# sch_output.net
KiCad netlist of a schematic drawn in Altium Designer
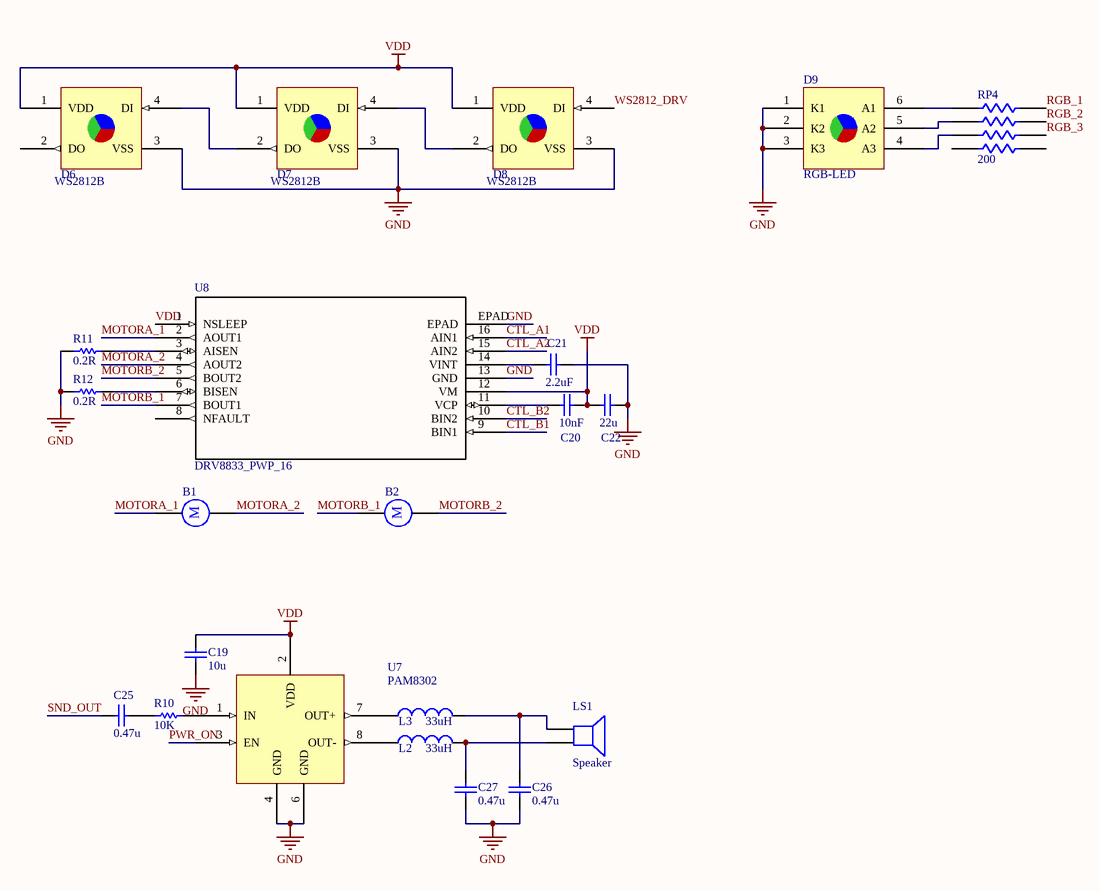
[diagram p0: sch_output.SchDoc]

(export (version "E")
  (design (tool "Eeschema 10.0.6"))
  (components
    (comp (ref "B1")
      (value "Motor")
      (footprint "RB5-10.5")
      (description "Motor, General Kind")
      (fields (field (name "PUBLISHER") "Altium Limited"))
      (libsource (lib "Miscellaneous Devices") (part "Motor"))
    )
    (comp (ref "B2")
      (value "Motor")
      (footprint "RB5-10.5")
      (description "Motor, General Kind")
      (fields (field (name "PUBLISHER") "Altium Limited"))
      (libsource (lib "Miscellaneous Devices") (part "Motor"))
    )
    (comp (ref "C19")
      (value "10u")
      (footprint "C-2012[0805]")
      (description "Capacitor (Semiconductor SIM Model)")
      (fields (field (name "Comment") "Cap Semi") (field (name "PUBLISHER") "Altium Limited"))
      (libsource (lib "Miscellaneous Devices") (part "Cap Semi"))
    )
    (comp (ref "C20")
      (value "10nF")
      (footprint "C-1608[0603]")
      (description "Capacitor (Semiconductor SIM Model)")
      (fields (field (name "Comment") "Cap Semi") (field (name "PUBLISHER") "Altium Limited"))
      (libsource (lib "Miscellaneous Devices") (part "Cap Semi"))
    )
    (comp (ref "C21")
      (value "2.2uF")
      (footprint "C-1608[0603]")
      (description "Capacitor (Semiconductor SIM Model)")
      (fields (field (name "Comment") "Cap Semi") (field (name "PUBLISHER") "Altium Limited"))
      (libsource (lib "Miscellaneous Devices") (part "Cap Semi"))
    )
    (comp (ref "C22")
      (value "22u")
      (footprint "C-2012[0805]")
      (description "Capacitor (Semiconductor SIM Model)")
      (fields (field (name "Comment") "Cap Semi") (field (name "PUBLISHER") "Altium Limited"))
      (libsource (lib "Miscellaneous Devices") (part "Cap Semi"))
    )
    (comp (ref "C25")
      (value "0.47u")
      (footprint "C-1608[0603]")
      (description "Capacitor (Semiconductor SIM Model)")
      (fields (field (name "Comment") "Cap Semi") (field (name "PUBLISHER") "Altium Limited"))
      (libsource (lib "Miscellaneous Devices") (part "Cap Semi"))
    )
    (comp (ref "C26")
      (value "0.47u")
      (footprint "C-1608[0603]")
      (description "Capacitor (Semiconductor SIM Model)")
      (fields (field (name "Comment") "Cap Semi") (field (name "PUBLISHER") "Altium Limited"))
      (libsource (lib "Miscellaneous Devices") (part "Cap Semi"))
    )
    (comp (ref "C27")
      (value "0.47u")
      (footprint "C-1608[0603]")
      (description "Capacitor (Semiconductor SIM Model)")
      (fields (field (name "Comment") "Cap Semi") (field (name "PUBLISHER") "Altium Limited"))
      (libsource (lib "Miscellaneous Devices") (part "Cap Semi"))
    )
    (comp (ref "D6") (value "WS2812B") (footprint "LED-5050-4") (libsource (lib "general") (part "WS2812B")))
    (comp (ref "D7") (value "WS2812B") (footprint "LED-5050-4") (libsource (lib "general") (part "WS2812B")))
    (comp (ref "D8") (value "WS2812B") (footprint "LED-5050-4") (libsource (lib "general") (part "WS2812B")))
    (comp (ref "D9") (value "RGB-LED") (footprint "LED-5050-6") (libsource (lib "general") (part "RGBLED")))
    (comp (ref "L2")
      (value "33uH")
      (footprint "L-1608[0603]")
      (description "Inductor")
      (fields (field (name "PUBLISHER") "Altium Limited"))
      (libsource (lib "Miscellaneous Devices") (part "Inductor"))
    )
    (comp (ref "L3")
      (value "33uH")
      (footprint "L-1608[0603]")
      (description "Inductor")
      (fields (field (name "PUBLISHER") "Altium Limited"))
      (libsource (lib "Miscellaneous Devices") (part "Inductor"))
    )
    (comp (ref "LS1")
      (value "Speaker")
      (footprint "PIN2")
      (description "Loudspeaker")
      (fields (field (name "PUBLISHER") "Altium Limited"))
      (libsource (lib "Miscellaneous Devices") (part "Speaker"))
    )
    (comp (ref "R10")
      (value "10K")
      (footprint "R-1608[0603]")
      (description "Semiconductor Resistor")
      (fields (field (name "Comment") "Res Semi") (field (name "PUBLISHER") "Altium Limited"))
      (libsource (lib "Miscellaneous Devices") (part "Res Semi"))
    )
    (comp (ref "R11")
      (value "0.2R")
      (footprint "R-3216[1206]")
      (description "Semiconductor Resistor")
      (fields (field (name "Comment") "Res Semi") (field (name "PUBLISHER") "Altium Limited"))
      (libsource (lib "Miscellaneous Devices") (part "Res Semi"))
    )
    (comp (ref "R12")
      (value "0.2R")
      (footprint "R-3216[1206]")
      (description "Semiconductor Resistor")
      (fields (field (name "Comment") "Res Semi") (field (name "PUBLISHER") "Altium Limited"))
      (libsource (lib "Miscellaneous Devices") (part "Res Semi"))
    )
    (comp (ref "RP4") (value "200") (footprint "R0603x4") (libsource (lib "general") (part "RPACK4")))
    (comp (ref "U7") (value "PAM8302") (footprint "SOP8-3D") (libsource (lib "general") (part "PAM8302")))
    (comp (ref "U8")
      (value "DRV8833_PWP_16")
      (footprint "PWP16_2P31X2P46")
      (description "Imported")
      (fields
        (field (name "MANUFACTURER") "Texas Instruments")
        (field (name "GENERIC_PART_NUMBER") "DRV8833")
      )
      (libsource (lib "DRV8833") (part "DRV8833_PWP_16"))
    )
  )
  (nets
    (net (code "1") (name "/CTL_A1") (class "Default")
      (node (ref "U8") (pin "16") (pinfunction "AIN1_16") (pintype "input"))
    )
    (net (code "2") (name "/CTL_A2") (class "Default")
      (node (ref "U8") (pin "15") (pinfunction "AIN2_15") (pintype "input"))
    )
    (net (code "3") (name "/CTL_B1") (class "Default")
      (node (ref "U8") (pin "9") (pinfunction "BIN1_9") (pintype "input"))
    )
    (net (code "4") (name "/CTL_B2") (class "Default")
      (node (ref "U8") (pin "10") (pinfunction "BIN2_10") (pintype "input"))
    )
    (net (code "5") (name "/MOTORA_1") (class "Default")
      (node (ref "B1") (pin "1") (pinfunction "1_1") (pintype "passive"))
      (node (ref "U8") (pin "2") (pinfunction "AOUT1_2") (pintype "output"))
    )
    (net (code "6") (name "/MOTORA_2") (class "Default")
      (node (ref "B1") (pin "2") (pinfunction "2_2") (pintype "passive"))
      (node (ref "U8") (pin "4") (pinfunction "AOUT2_4") (pintype "output"))
    )
    (net (code "7") (name "/MOTORB_1") (class "Default")
      (node (ref "B2") (pin "1") (pinfunction "1_1") (pintype "passive"))
      (node (ref "U8") (pin "7") (pinfunction "BOUT1_7") (pintype "output"))
    )
    (net (code "8") (name "/MOTORB_2") (class "Default")
      (node (ref "B2") (pin "2") (pinfunction "2_2") (pintype "passive"))
      (node (ref "U8") (pin "5") (pinfunction "BOUT2_5") (pintype "output"))
    )
    (net (code "9") (name "/PWR_ON") (class "Default")
      (node (ref "U7") (pin "3") (pinfunction "EN_3") (pintype "input"))
    )
    (net (code "10") (name "/RGB_1") (class "Default")
      (node (ref "RP4") (pin "8") (pinfunction "8_8") (pintype "passive"))
    )
    (net (code "11") (name "/RGB_2") (class "Default")
      (node (ref "RP4") (pin "7") (pinfunction "7_7") (pintype "passive"))
    )
    (net (code "12") (name "/RGB_3") (class "Default")
      (node (ref "RP4") (pin "6") (pinfunction "6_6") (pintype "passive"))
    )
    (net (code "13") (name "/SND_OUT") (class "Default")
      (node (ref "C25") (pin "2") (pinfunction "2_2") (pintype "passive"))
    )
    (net (code "14") (name "/WS2812_DRV") (class "Default")
      (node (ref "D8") (pin "4") (pinfunction "DI_4") (pintype "input"))
    )
    (net (code "15") (name "GND") (class "Default")
      (node (ref "C19") (pin "1") (pinfunction "1_1") (pintype "passive"))
      (node (ref "C21") (pin "1") (pinfunction "1_1") (pintype "passive"))
      (node (ref "C22") (pin "2") (pinfunction "2_2") (pintype "passive"))
      (node (ref "C26") (pin "2") (pinfunction "2_2") (pintype "passive"))
      (node (ref "C27") (pin "2") (pinfunction "2_2") (pintype "passive"))
      (node (ref "D6") (pin "3") (pinfunction "VSS_3") (pintype "power_in"))
      (node (ref "D7") (pin "3") (pinfunction "VSS_3") (pintype "power_in"))
      (node (ref "D8") (pin "3") (pinfunction "VSS_3") (pintype "power_in"))
      (node (ref "D9") (pin "1") (pinfunction "K1_1") (pintype "passive"))
      (node (ref "D9") (pin "2") (pinfunction "K2_2") (pintype "passive"))
      (node (ref "D9") (pin "3") (pinfunction "K3_3") (pintype "power_in"))
      (node (ref "R11") (pin "1") (pinfunction "1_1") (pintype "passive"))
      (node (ref "R12") (pin "1") (pinfunction "1_1") (pintype "passive"))
      (node (ref "U7") (pin "4") (pinfunction "GND_4") (pintype "power_in"))
      (node (ref "U7") (pin "6") (pinfunction "GND_6") (pintype "power_in"))
      (node (ref "U8") (pin "13") (pinfunction "GND_13") (pintype "power_in"))
      (node (ref "U8") (pin "EPAD") (pinfunction "EPAD_EPAD") (pintype "passive"))
    )
    (net (code "16") (name "Net-(C25-Pad1)") (class "Default")
      (node (ref "C25") (pin "1") (pinfunction "1_1") (pintype "passive"))
      (node (ref "R10") (pin "2") (pinfunction "2_2") (pintype "passive"))
    )
    (net (code "17") (name "Net-(C26-Pad1)") (class "Default")
      (node (ref "C26") (pin "1") (pinfunction "1_1") (pintype "passive"))
      (node (ref "L3") (pin "2") (pinfunction "2_2") (pintype "passive"))
      (node (ref "LS1") (pin "1") (pinfunction "1_1") (pintype "passive"))
    )
    (net (code "18") (name "Net-(C27-Pad1)") (class "Default")
      (node (ref "C27") (pin "1") (pinfunction "1_1") (pintype "passive"))
      (node (ref "L2") (pin "2") (pinfunction "2_2") (pintype "passive"))
      (node (ref "LS1") (pin "2") (pinfunction "2_2") (pintype "passive"))
    )
    (net (code "19") (name "Net-(D6-DI)") (class "Default")
      (node (ref "D6") (pin "4") (pinfunction "DI_4") (pintype "input"))
      (node (ref "D7") (pin "2") (pinfunction "DO_2") (pintype "output"))
    )
    (net (code "20") (name "Net-(D7-DI)") (class "Default")
      (node (ref "D7") (pin "4") (pinfunction "DI_4") (pintype "input"))
      (node (ref "D8") (pin "2") (pinfunction "DO_2") (pintype "output"))
    )
    (net (code "21") (name "Net-(D9-A1)") (class "Default")
      (node (ref "D9") (pin "6") (pinfunction "A1_6") (pintype "passive"))
      (node (ref "RP4") (pin "1") (pinfunction "1_1") (pintype "passive"))
    )
    (net (code "22") (name "Net-(D9-A2)") (class "Default")
      (node (ref "D9") (pin "5") (pinfunction "A2_5") (pintype "passive"))
      (node (ref "RP4") (pin "2") (pinfunction "2_2") (pintype "passive"))
    )
    (net (code "23") (name "Net-(D9-A3)") (class "Default")
      (node (ref "D9") (pin "4") (pinfunction "A3_4") (pintype "passive"))
      (node (ref "RP4") (pin "3") (pinfunction "3_3") (pintype "passive"))
    )
    (net (code "24") (name "Net-(U7-IN)") (class "Default")
      (node (ref "R10") (pin "1") (pinfunction "1_1") (pintype "passive"))
      (node (ref "U7") (pin "1") (pinfunction "IN_1") (pintype "input"))
    )
    (net (code "25") (name "Net-(U7-OUT+)") (class "Default")
      (node (ref "L3") (pin "1") (pinfunction "1_1") (pintype "passive"))
      (node (ref "U7") (pin "7") (pinfunction "OUT+_7") (pintype "output"))
    )
    (net (code "26") (name "Net-(U7-OUT-)") (class "Default")
      (node (ref "L2") (pin "1") (pinfunction "1_1") (pintype "passive"))
      (node (ref "U7") (pin "8") (pinfunction "OUT-_8") (pintype "output"))
    )
    (net (code "27") (name "Net-(U8-AISEN)") (class "Default")
      (node (ref "R11") (pin "2") (pinfunction "2_2") (pintype "passive"))
      (node (ref "U8") (pin "3") (pinfunction "AISEN_3") (pintype "bidirectional"))
    )
    (net (code "28") (name "Net-(U8-BISEN)") (class "Default")
      (node (ref "R12") (pin "2") (pinfunction "2_2") (pintype "passive"))
      (node (ref "U8") (pin "6") (pinfunction "BISEN_6") (pintype "bidirectional"))
    )
    (net (code "29") (name "Net-(U8-VCP)") (class "Default")
      (node (ref "C20") (pin "2") (pinfunction "2_2") (pintype "passive"))
      (node (ref "U8") (pin "11") (pinfunction "VCP_11") (pintype "bidirectional"))
    )
    (net (code "30") (name "Net-(U8-VINT)") (class "Default")
      (node (ref "C21") (pin "2") (pinfunction "2_2") (pintype "passive"))
      (node (ref "U8") (pin "14") (pinfunction "VINT_14") (pintype "power_in"))
    )
    (net (code "31") (name "VDD") (class "Default")
      (node (ref "C19") (pin "2") (pinfunction "2_2") (pintype "passive"))
      (node (ref "C20") (pin "1") (pinfunction "1_1") (pintype "passive"))
      (node (ref "C22") (pin "1") (pinfunction "1_1") (pintype "passive"))
      (node (ref "D6") (pin "1") (pinfunction "VDD_1") (pintype "power_in"))
      (node (ref "D7") (pin "1") (pinfunction "VDD_1") (pintype "power_in"))
      (node (ref "D8") (pin "1") (pinfunction "VDD_1") (pintype "power_in"))
      (node (ref "U7") (pin "2") (pinfunction "VDD_2") (pintype "power_in"))
      (node (ref "U8") (pin "1") (pinfunction "NSLEEP_1") (pintype "input"))
      (node (ref "U8") (pin "12") (pinfunction "VM_12") (pintype "power_in"))
    )
    (net (code "32") (name "unconnected-(D6-DO-Pad2)") (class "Default")
      (node (ref "D6") (pin "2") (pinfunction "DO_2") (pintype "output"))
    )
    (net (code "33") (name "unconnected-(RP4-Pad4)") (class "Default")
      (node (ref "RP4") (pin "4") (pinfunction "4_4") (pintype "passive"))
    )
    (net (code "34") (name "unconnected-(RP4-Pad5)") (class "Default")
      (node (ref "RP4") (pin "5") (pinfunction "5_5") (pintype "passive"))
    )
    (net (code "35") (name "unconnected-(U8-NFAULT-Pad8)") (class "Default")
      (node (ref "U8") (pin "8") (pinfunction "NFAULT_8") (pintype "output"))
    )
  )
)
